# TLV62569_SingleChannel.net
KiCad netlist of a schematic drawn in Altium Designer
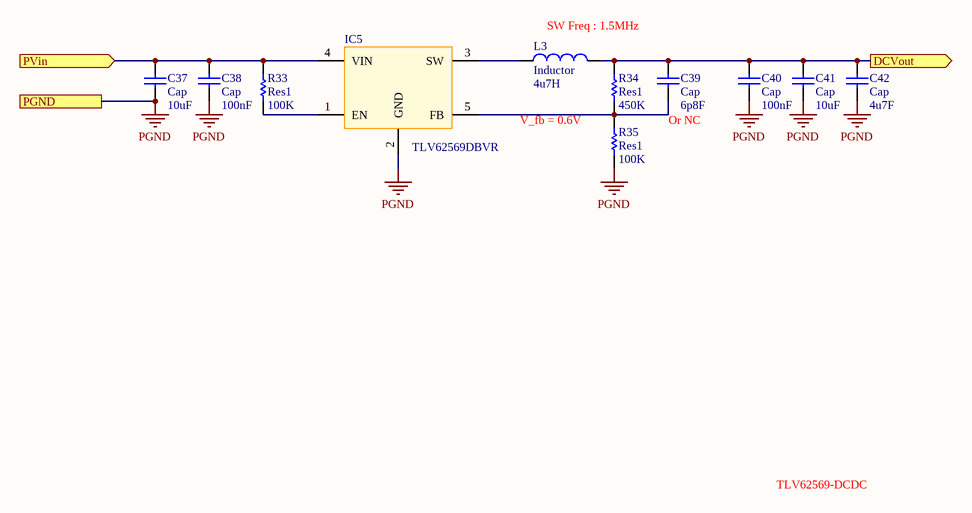
[diagram p0: TLV62569_SingleChannel.SchDoc]

(export (version "E")
  (design (tool "Eeschema 10.0.6"))
  (components
    (comp (ref "C37")
      (value "Cap")
      (footprint "0603C")
      (description "Capacitor")
      (fields (field (name "ALTIUM_VALUE") "10uF") (field (name "PUBLISHER") "Altium Limited"))
      (libsource (lib "Miscellaneous Devices") (part "Cap"))
    )
    (comp (ref "C38")
      (value "Cap")
      (footprint "0603C")
      (description "Capacitor")
      (fields (field (name "ALTIUM_VALUE") "100nF") (field (name "PUBLISHER") "Altium Limited"))
      (libsource (lib "Miscellaneous Devices") (part "Cap"))
    )
    (comp (ref "C39")
      (value "Cap")
      (footprint "0603C")
      (description "Capacitor")
      (fields (field (name "ALTIUM_VALUE") "6p8F") (field (name "PUBLISHER") "Altium Limited"))
      (libsource (lib "Miscellaneous Devices") (part "Cap"))
    )
    (comp (ref "C40")
      (value "Cap")
      (footprint "0603C")
      (description "Capacitor")
      (fields (field (name "ALTIUM_VALUE") "100nF") (field (name "PUBLISHER") "Altium Limited"))
      (libsource (lib "Miscellaneous Devices") (part "Cap"))
    )
    (comp (ref "C41")
      (value "Cap")
      (footprint "0603C")
      (description "Capacitor")
      (fields (field (name "ALTIUM_VALUE") "10uF") (field (name "PUBLISHER") "Altium Limited"))
      (libsource (lib "Miscellaneous Devices") (part "Cap"))
    )
    (comp (ref "C42")
      (value "Cap")
      (footprint "0603C")
      (description "Capacitor")
      (fields (field (name "ALTIUM_VALUE") "4u7F") (field (name "PUBLISHER") "Altium Limited"))
      (libsource (lib "Miscellaneous Devices") (part "Cap"))
    )
    (comp (ref "IC5")
      (value "TLV62569DBVR")
      (footprint "脉诊:SOT95P280X145-5N")
      (fields (field (name "MOUSER PART NUMBER") "595-TLV62569DBVR"))
      (libsource (lib "脉诊") (part "TLV62569DBVR"))
    )
    (comp (ref "L3")
      (value "Inductor")
      (footprint "0402-A")
      (fields (field (name "ALTIUM_VALUE") "4u7H") (field (name "PUBLISHER") "Altium Limited"))
      (libsource (lib "Miscellaneous Devices") (part "Inductor"))
    )
    (comp (ref "R33")
      (value "Res1")
      (footprint "0603R")
      (description "Resistor")
      (fields (field (name "ALTIUM_VALUE") "100K") (field (name "PUBLISHER") "Altium Limited"))
      (libsource (lib "Miscellaneous Devices") (part "Res1"))
    )
    (comp (ref "R34")
      (value "Res1")
      (footprint "0603R")
      (description "Resistor")
      (fields (field (name "ALTIUM_VALUE") "450K") (field (name "PUBLISHER") "Altium Limited"))
      (libsource (lib "Miscellaneous Devices") (part "Res1"))
    )
    (comp (ref "R35")
      (value "Res1")
      (footprint "0603R")
      (description "Resistor")
      (fields (field (name "ALTIUM_VALUE") "100K") (field (name "PUBLISHER") "Altium Limited"))
      (libsource (lib "Miscellaneous Devices") (part "Res1"))
    )
  )
  (nets
    (net (code "1") (name "/DCVout") (class "Default")
      (node (ref "C39") (pin "2") (pinfunction "2_2") (pintype "passive"))
      (node (ref "C40") (pin "2") (pinfunction "2_2") (pintype "passive"))
      (node (ref "C41") (pin "2") (pinfunction "2_2") (pintype "passive"))
      (node (ref "C42") (pin "2") (pinfunction "2_2") (pintype "passive"))
      (node (ref "L3") (pin "2") (pinfunction "2_2") (pintype "passive"))
      (node (ref "R34") (pin "2") (pinfunction "2_2") (pintype "passive"))
    )
    (net (code "2") (name "/PVin") (class "Default")
      (node (ref "C37") (pin "2") (pinfunction "2_2") (pintype "passive"))
      (node (ref "C38") (pin "2") (pinfunction "2_2") (pintype "passive"))
      (node (ref "IC5") (pin "4") (pinfunction "VIN_4") (pintype "passive"))
      (node (ref "R33") (pin "2") (pinfunction "2_2") (pintype "passive"))
    )
    (net (code "3") (name "Net-(IC5-EN)") (class "Default")
      (node (ref "IC5") (pin "1") (pinfunction "EN_1") (pintype "passive"))
      (node (ref "R33") (pin "1") (pinfunction "1_1") (pintype "passive"))
    )
    (net (code "4") (name "Net-(IC5-FB)") (class "Default")
      (node (ref "C39") (pin "1") (pinfunction "1_1") (pintype "passive"))
      (node (ref "IC5") (pin "5") (pinfunction "FB_5") (pintype "passive"))
      (node (ref "R34") (pin "1") (pinfunction "1_1") (pintype "passive"))
      (node (ref "R35") (pin "2") (pinfunction "2_2") (pintype "passive"))
    )
    (net (code "5") (name "Net-(IC5-SW)") (class "Default")
      (node (ref "IC5") (pin "3") (pinfunction "SW_3") (pintype "passive"))
      (node (ref "L3") (pin "1") (pinfunction "1_1") (pintype "passive"))
    )
    (net (code "6") (name "PGND") (class "Default")
      (node (ref "C37") (pin "1") (pinfunction "1_1") (pintype "passive"))
      (node (ref "C38") (pin "1") (pinfunction "1_1") (pintype "passive"))
      (node (ref "C40") (pin "1") (pinfunction "1_1") (pintype "passive"))
      (node (ref "C41") (pin "1") (pinfunction "1_1") (pintype "passive"))
      (node (ref "C42") (pin "1") (pinfunction "1_1") (pintype "passive"))
      (node (ref "IC5") (pin "2") (pinfunction "GND_2") (pintype "passive"))
      (node (ref "R35") (pin "1") (pinfunction "1_1") (pintype "passive"))
    )
  )
)
